# 06_Analog_and_Motor.net
KiCad netlist of a schematic drawn in Altium Designer
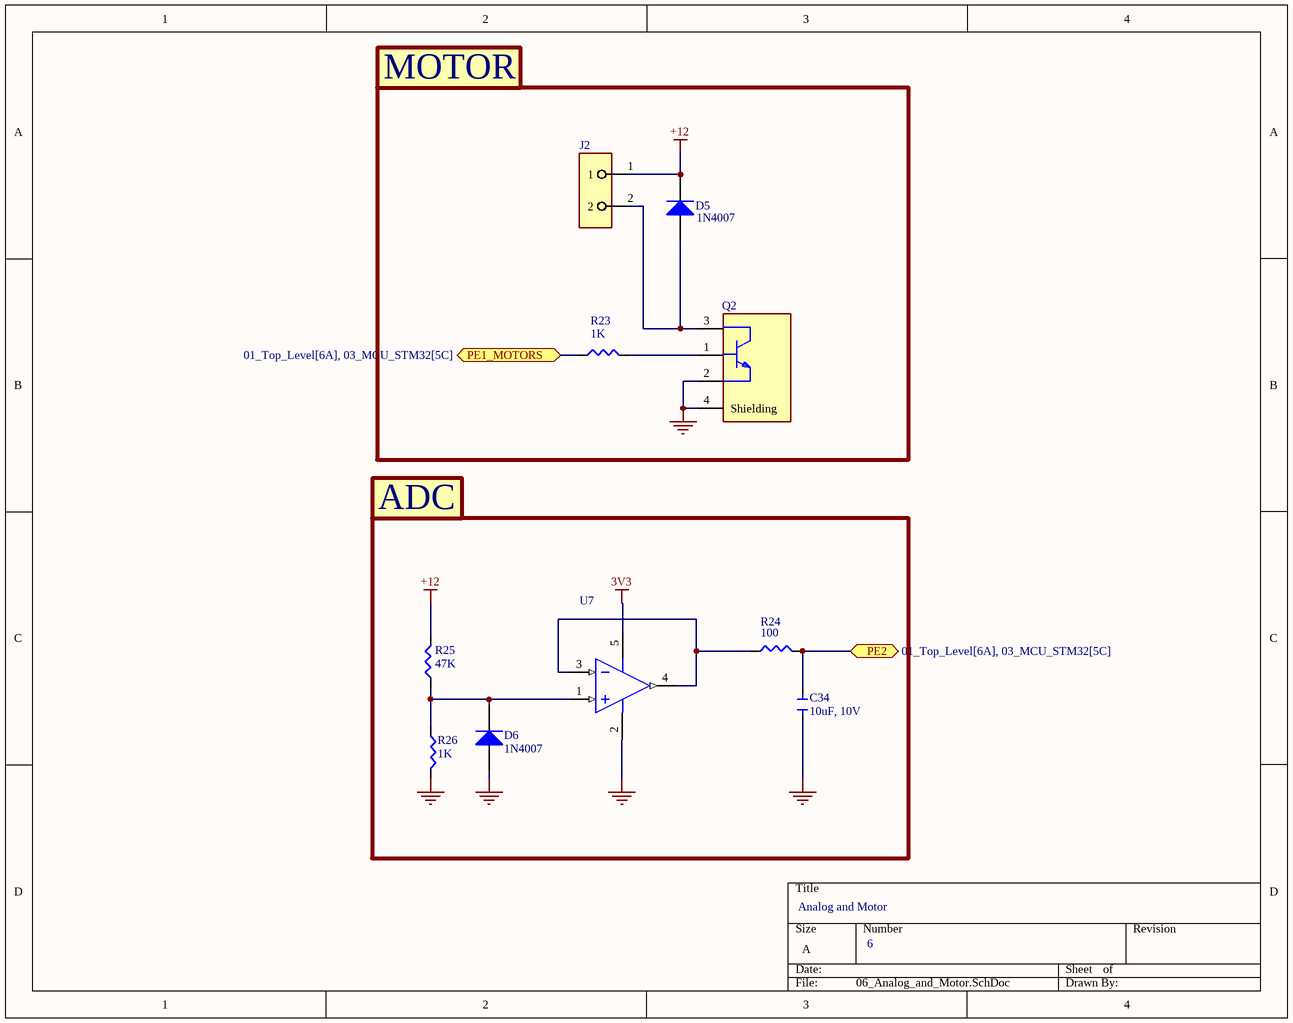
[diagram p0: 06_Analog_and_Motor.SchDoc]

(export (version "E")
  (design (tool "Eeschema 10.0.6"))
  (components
    (comp (ref "C34")
      (value "10uF, 10V")
      (footprint "CAP_10uF")
      (description "CAP CER 10UF 10V X5R 0402")
      (fields
        (field (name "MANUFACTURER") "Samsung Electro-Mechanics")
        (field (name "MANUFACTURER PART NUMBER") "C307415")
      )
      (libsource (lib "Components_Schlib") (part "CAP_0402_10UF"))
    )
    (comp (ref "D5")
      (value "1N4007")
      (footprint "FAIR-DO-41-2")
      (description "General Purpose Rectifier, 1.1 V, 1.0 A, -55 to 175 degC, 2-Pin DO-41, RoHS, Tape and Reel")
      (fields (field (name "MANUFACTURER") "Fairchild"))
      (libsource (lib "Youssef Adel") (part "KESE-D_K1A2-2"))
    )
    (comp (ref "D6")
      (value "1N4007")
      (footprint "FAIR-DO-41-2")
      (description "General Purpose Rectifier, 1.1 V, 1.0 A, -55 to 175 degC, 2-Pin DO-41, RoHS, Tape and Reel")
      (fields (field (name "MANUFACTURER") "Fairchild"))
      (libsource (lib "Youssef Adel") (part "KESE-D_K1A2-2"))
    )
    (comp (ref "J2")
      (value "43640-0201")
      (footprint "FP-43640-0201-MFG")
      (description "CONN PLUG 2POS 3MM SINGLE ROW")
      (libsource (lib "Components_Schlib") (part "CMP-04776-000134-1"))
    )
    (comp (ref "Q2")
      (value "JANTX2N2222AUB/TR")
      (footprint "FP-UB-IPC_A")
      (description "JANTX2N2222AUB/TR Trans Gp Bjt NPN 50V 0.8A 3-PIN Ub T/r")
      (libsource (lib "Altium Content Vault") (part "580d0d82e5fdcb6997091161ed5c1cf"))
    )
    (comp (ref "R23")
      (value "1K")
      (footprint "RES_2K")
      (description "100mW 2KΩ 75V Thick Film Resistor ±100ppm/℃ ±1% 0603 Chip Resistor - Surface Mount RoHS")
      (libsource (lib "Components_Schlib") (part "RSE_0603_2K"))
    )
    (comp (ref "R24")
      (value "100")
      (footprint "RES_2K")
      (description "100mW 2KΩ 75V Thick Film Resistor ±100ppm/℃ ±1% 0603 Chip Resistor - Surface Mount RoHS")
      (libsource (lib "Components_Schlib") (part "RSE_0603_2K"))
    )
    (comp (ref "R25")
      (value "47K")
      (footprint "RES_2K")
      (description "100mW 2KΩ 75V Thick Film Resistor ±100ppm/℃ ±1% 0603 Chip Resistor - Surface Mount RoHS")
      (libsource (lib "Components_Schlib") (part "RSE_0603_2K"))
    )
    (comp (ref "R26")
      (value "1K")
      (footprint "RES_2K")
      (description "100mW 2KΩ 75V Thick Film Resistor ±100ppm/℃ ±1% 0603 Chip Resistor - Surface Mount RoHS")
      (libsource (lib "Components_Schlib") (part "RSE_0603_2K"))
    )
    (comp (ref "U7")
      (value "LMV321SN3T1G")
      (footprint "ONSC-TSOP-5-483-02_V")
      (fields (field (name "MANUFACTURER") "On Semiconductor"))
      (libsource (lib "Altium Content Vault") (part "ONSC-LMV321-TSOP-5-483-02"))
    )
  )
  (nets
    (net (code "1") (name "+12") (class "Default")
      (node (ref "D5") (pin "1") (pinfunction "K_1") (pintype "passive"))
      (node (ref "J2") (pin "1") (pinfunction "1_1") (pintype "passive"))
      (node (ref "R25") (pin "2") (pinfunction "2_2") (pintype "passive"))
    )
    (net (code "2") (name "/PE1_MOTORS") (class "Default")
      (node (ref "R23") (pin "1") (pinfunction "1_1") (pintype "passive"))
    )
    (net (code "3") (name "/PE2") (class "Default")
      (node (ref "C34") (pin "2") (pinfunction "2_2") (pintype "passive"))
      (node (ref "R24") (pin "2") (pinfunction "2_2") (pintype "passive"))
    )
    (net (code "4") (name "3V3") (class "Default")
      (node (ref "U7") (pin "5") (pinfunction "V+_5") (pintype "power_in"))
    )
    (net (code "5") (name "GND") (class "Default")
      (node (ref "C34") (pin "1") (pinfunction "1_1") (pintype "passive"))
      (node (ref "D6") (pin "2") (pinfunction "A_2") (pintype "passive"))
      (node (ref "Q2") (pin "2") (pinfunction "E_2") (pintype "passive"))
      (node (ref "Q2") (pin "4") (pinfunction "Shielding_4") (pintype "passive"))
      (node (ref "R26") (pin "2") (pinfunction "2_2") (pintype "passive"))
      (node (ref "U7") (pin "2") (pinfunction "V-_2") (pintype "power_in"))
    )
    (net (code "6") (name "Net-(D5-A)") (class "Default")
      (node (ref "D5") (pin "2") (pinfunction "A_2") (pintype "passive"))
      (node (ref "J2") (pin "2") (pinfunction "2_2") (pintype "passive"))
      (node (ref "Q2") (pin "3") (pinfunction "C_3") (pintype "passive"))
    )
    (net (code "7") (name "Net-(D6-K)") (class "Default")
      (node (ref "D6") (pin "1") (pinfunction "K_1") (pintype "passive"))
      (node (ref "R25") (pin "1") (pinfunction "1_1") (pintype "passive"))
      (node (ref "R26") (pin "1") (pinfunction "1_1") (pintype "passive"))
      (node (ref "U7") (pin "1") (pinfunction "IN+_1") (pintype "input"))
    )
    (net (code "8") (name "Net-(Q2-B)") (class "Default")
      (node (ref "Q2") (pin "1") (pinfunction "B_1") (pintype "passive"))
      (node (ref "R23") (pin "2") (pinfunction "2_2") (pintype "passive"))
    )
    (net (code "9") (name "Net-(U7-IN-)") (class "Default")
      (node (ref "R24") (pin "1") (pinfunction "1_1") (pintype "passive"))
      (node (ref "U7") (pin "3") (pinfunction "IN-_3") (pintype "input"))
      (node (ref "U7") (pin "4") (pinfunction "OUT_4") (pintype "output"))
    )
  )
)
